# Motor.net
KiCad netlist of a schematic drawn in Altium Designer
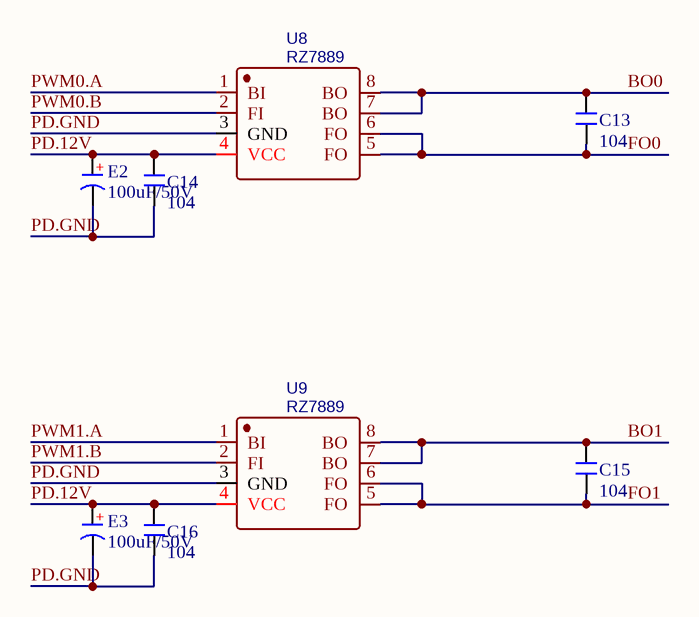
[diagram p0: Motor.SchDoc]

(export (version "E")
  (design (tool "Eeschema 10.0.6"))
  (components
    (comp (ref "C13")
      (value "104")
      (footprint "C 0603")
      (description "无极性贴片电容")
      (fields (field (name "版权归属") "源创客"))
      (libsource (lib "3.1   - 电阻-电容-电感") (part "C"))
    )
    (comp (ref "C14")
      (value "104")
      (footprint "C 0603")
      (description "无极性贴片电容")
      (fields (field (name "版权归属") "源创客"))
      (libsource (lib "3.1   - 电阻-电容-电感") (part "C"))
    )
    (comp (ref "C15")
      (value "104")
      (footprint "C 0603")
      (description "无极性贴片电容")
      (fields (field (name "版权归属") "源创客"))
      (libsource (lib "3.1   - 电阻-电容-电感") (part "C"))
    )
    (comp (ref "C16")
      (value "104")
      (footprint "C 0603")
      (description "无极性贴片电容")
      (fields (field (name "版权归属") "源创客"))
      (libsource (lib "3.1   - 电阻-电容-电感") (part "C"))
    )
    (comp (ref "E2")
      (value "100uF/50V")
      (footprint "CM F(10*10.2)")
      (description "贴片电解电容")
      (fields (field (name "版权归属") "源创客"))
      (libsource (lib "电阻-电容-电感") (part "C-CM"))
    )
    (comp (ref "E3")
      (value "100uF/50V")
      (footprint "CM F(10*10.2)")
      (description "贴片电解电容")
      (fields (field (name "版权归属") "源创客"))
      (libsource (lib "电阻-电容-电感") (part "C-CM"))
    )
    (comp (ref "U8")
      (value "RZ7889")
      (footprint "SOP8_L")
      (fields (field (name "BOM_SUPPLIER PART") "C83668"))
      (libsource (lib "altium-import") (part "root_0_RZ7889_"))
    )
    (comp (ref "U9")
      (value "RZ7889")
      (footprint "SOP8_L")
      (fields (field (name "BOM_SUPPLIER PART") "C83668"))
      (libsource (lib "altium-import") (part "root_0_RZ7889_"))
    )
  )
  (nets
    (net (code "1") (name "/BO0") (class "Default")
      (node (ref "C13") (pin "2") (pinfunction "2_2") (pintype "passive"))
      (node (ref "U8") (pin "7") (pinfunction "BO_7") (pintype "passive"))
      (node (ref "U8") (pin "8") (pinfunction "BO_8") (pintype "passive"))
    )
    (net (code "2") (name "/BO1") (class "Default")
      (node (ref "C15") (pin "2") (pinfunction "2_2") (pintype "passive"))
      (node (ref "U9") (pin "7") (pinfunction "BO_7") (pintype "passive"))
      (node (ref "U9") (pin "8") (pinfunction "BO_8") (pintype "passive"))
    )
    (net (code "3") (name "/FO0") (class "Default")
      (node (ref "C13") (pin "1") (pinfunction "1_1") (pintype "passive"))
      (node (ref "U8") (pin "5") (pinfunction "FO_5") (pintype "passive"))
      (node (ref "U8") (pin "6") (pinfunction "FO_6") (pintype "passive"))
    )
    (net (code "4") (name "/FO1") (class "Default")
      (node (ref "C15") (pin "1") (pinfunction "1_1") (pintype "passive"))
      (node (ref "U9") (pin "5") (pinfunction "FO_5") (pintype "passive"))
      (node (ref "U9") (pin "6") (pinfunction "FO_6") (pintype "passive"))
    )
    (net (code "5") (name "/PD.12V") (class "Default")
      (node (ref "C14") (pin "2") (pinfunction "2_2") (pintype "passive"))
      (node (ref "C16") (pin "2") (pinfunction "2_2") (pintype "passive"))
      (node (ref "E2") (pin "1") (pinfunction "A_1") (pintype "passive"))
      (node (ref "E3") (pin "1") (pinfunction "A_1") (pintype "passive"))
      (node (ref "U8") (pin "4") (pinfunction "VCC_4") (pintype "passive"))
      (node (ref "U9") (pin "4") (pinfunction "VCC_4") (pintype "passive"))
    )
    (net (code "6") (name "/PD.GND") (class "Default")
      (node (ref "C14") (pin "1") (pinfunction "1_1") (pintype "passive"))
      (node (ref "C16") (pin "1") (pinfunction "1_1") (pintype "passive"))
      (node (ref "E2") (pin "2") (pinfunction "K_2") (pintype "passive"))
      (node (ref "E3") (pin "2") (pinfunction "K_2") (pintype "passive"))
      (node (ref "U8") (pin "3") (pinfunction "GND_3") (pintype "passive"))
      (node (ref "U9") (pin "3") (pinfunction "GND_3") (pintype "passive"))
    )
    (net (code "7") (name "/PWM0.A") (class "Default")
      (node (ref "U8") (pin "1") (pinfunction "BI_1") (pintype "passive"))
    )
    (net (code "8") (name "/PWM0.B") (class "Default")
      (node (ref "U8") (pin "2") (pinfunction "FI_2") (pintype "passive"))
    )
    (net (code "9") (name "/PWM1.A") (class "Default")
      (node (ref "U9") (pin "1") (pinfunction "BI_1") (pintype "passive"))
    )
    (net (code "10") (name "/PWM1.B") (class "Default")
      (node (ref "U9") (pin "2") (pinfunction "FI_2") (pintype "passive"))
    )
  )
)
